# ascender_board.net
KiCad netlist of a schematic drawn in EAGLE
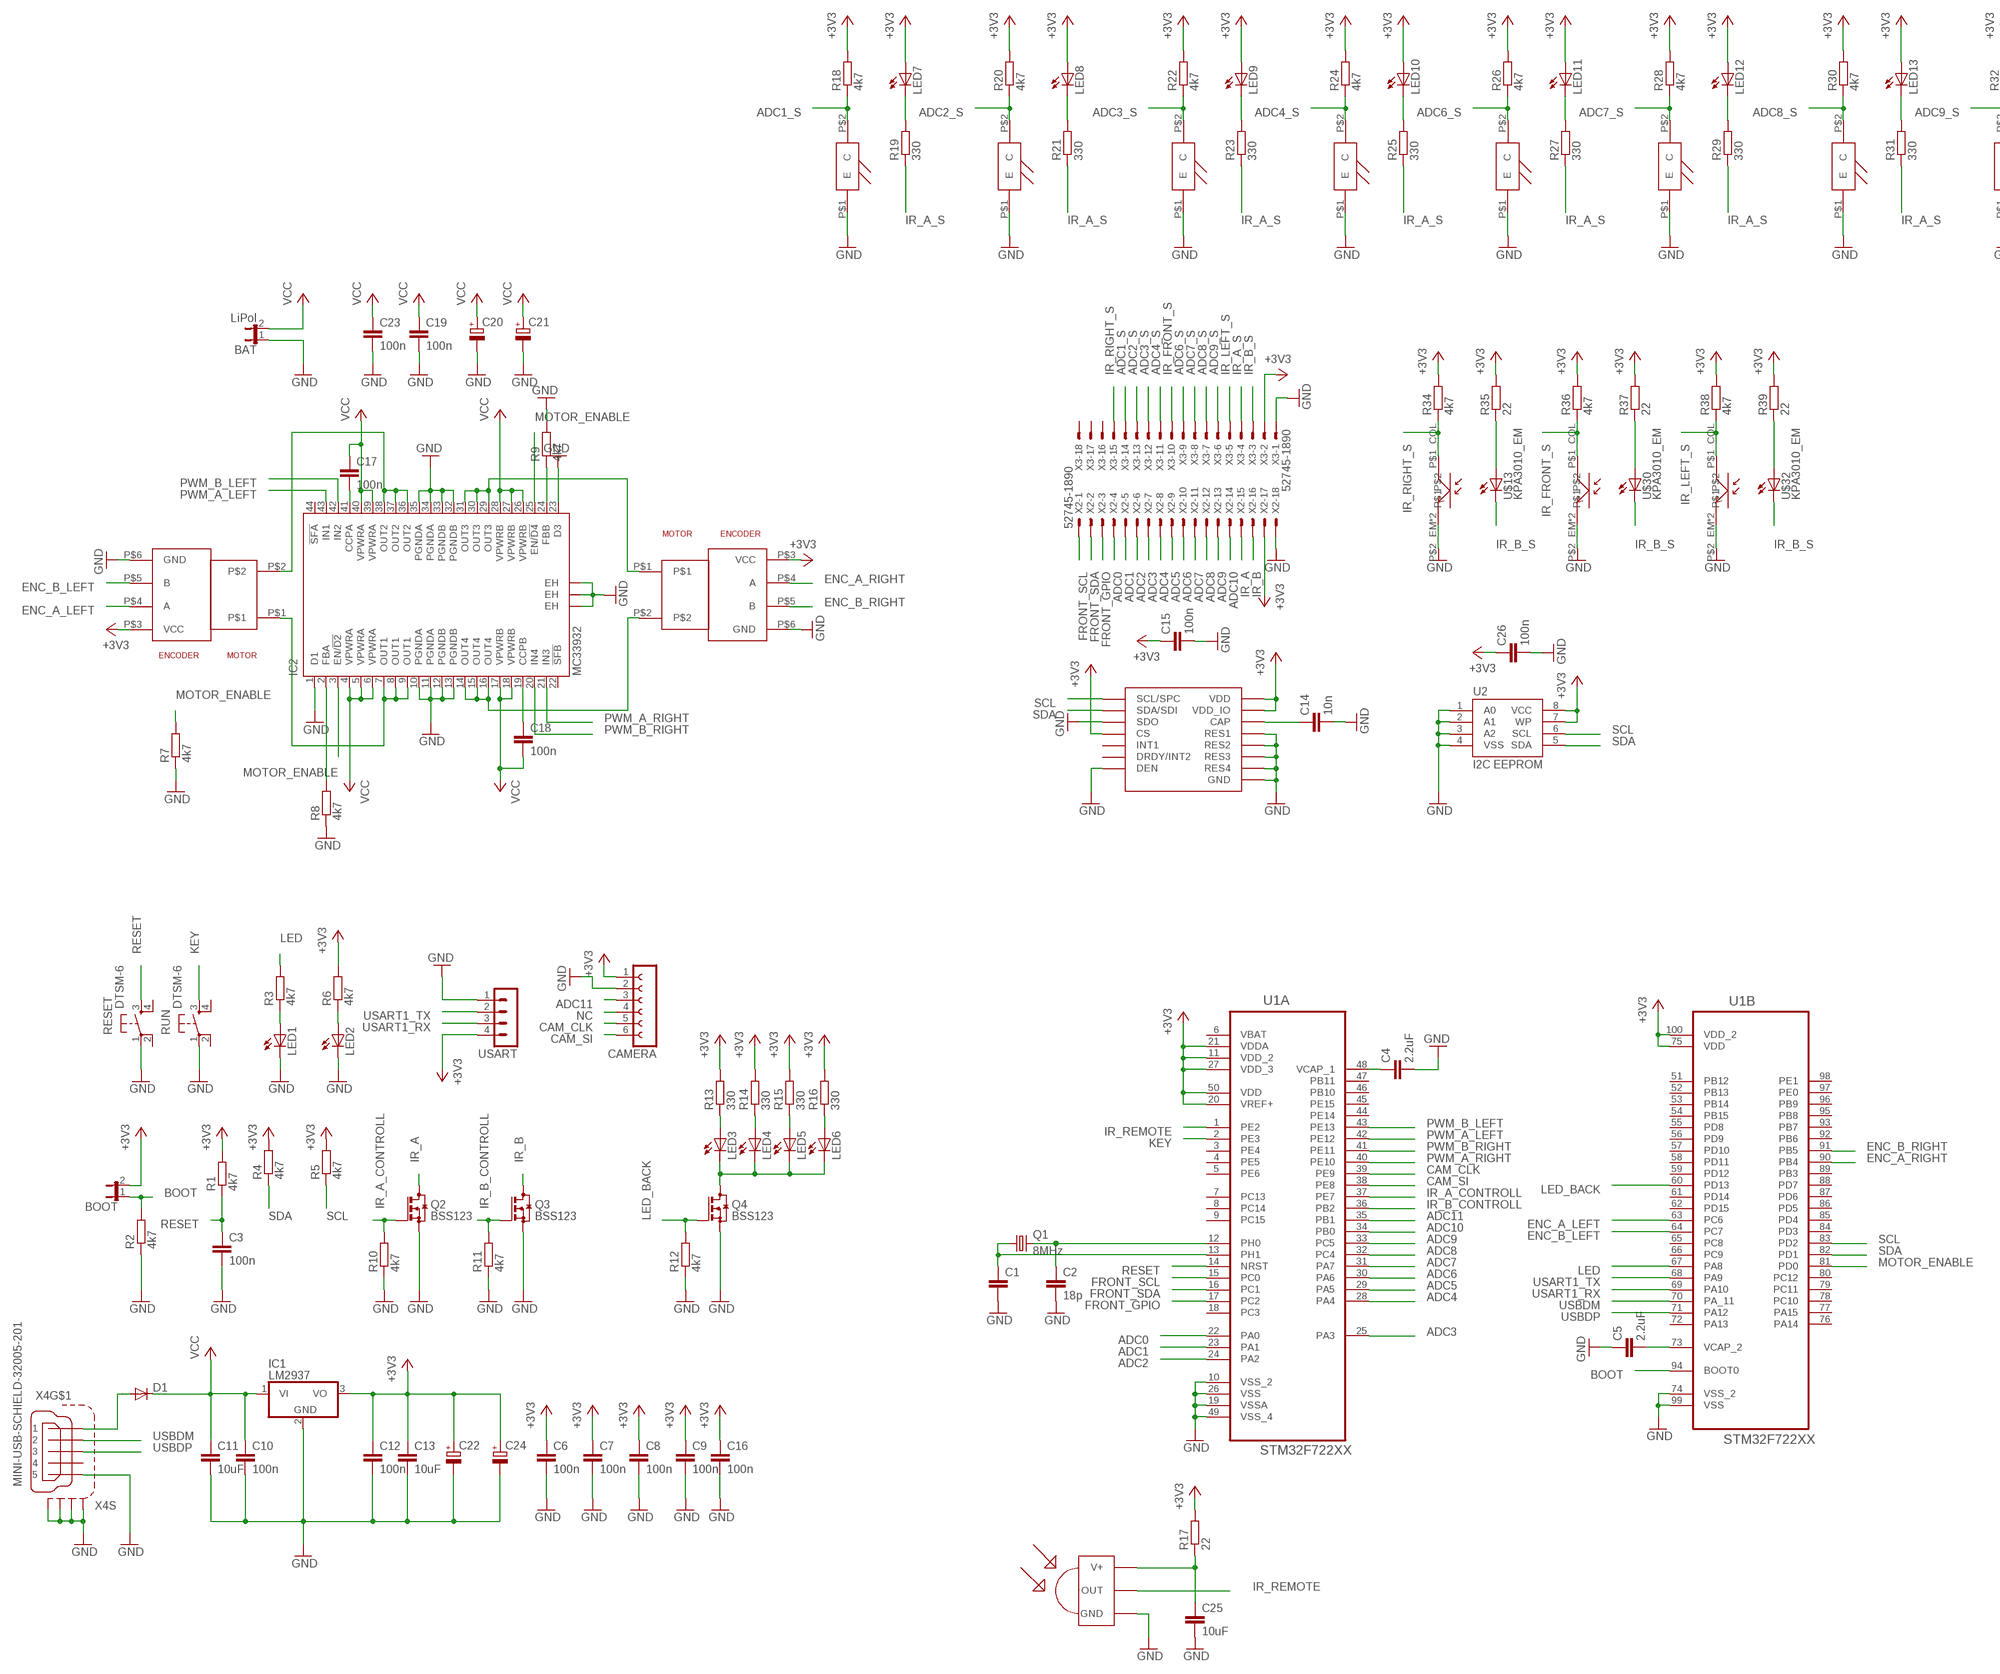
[diagram p0: schematic, sheet 1, part 1 of 2]
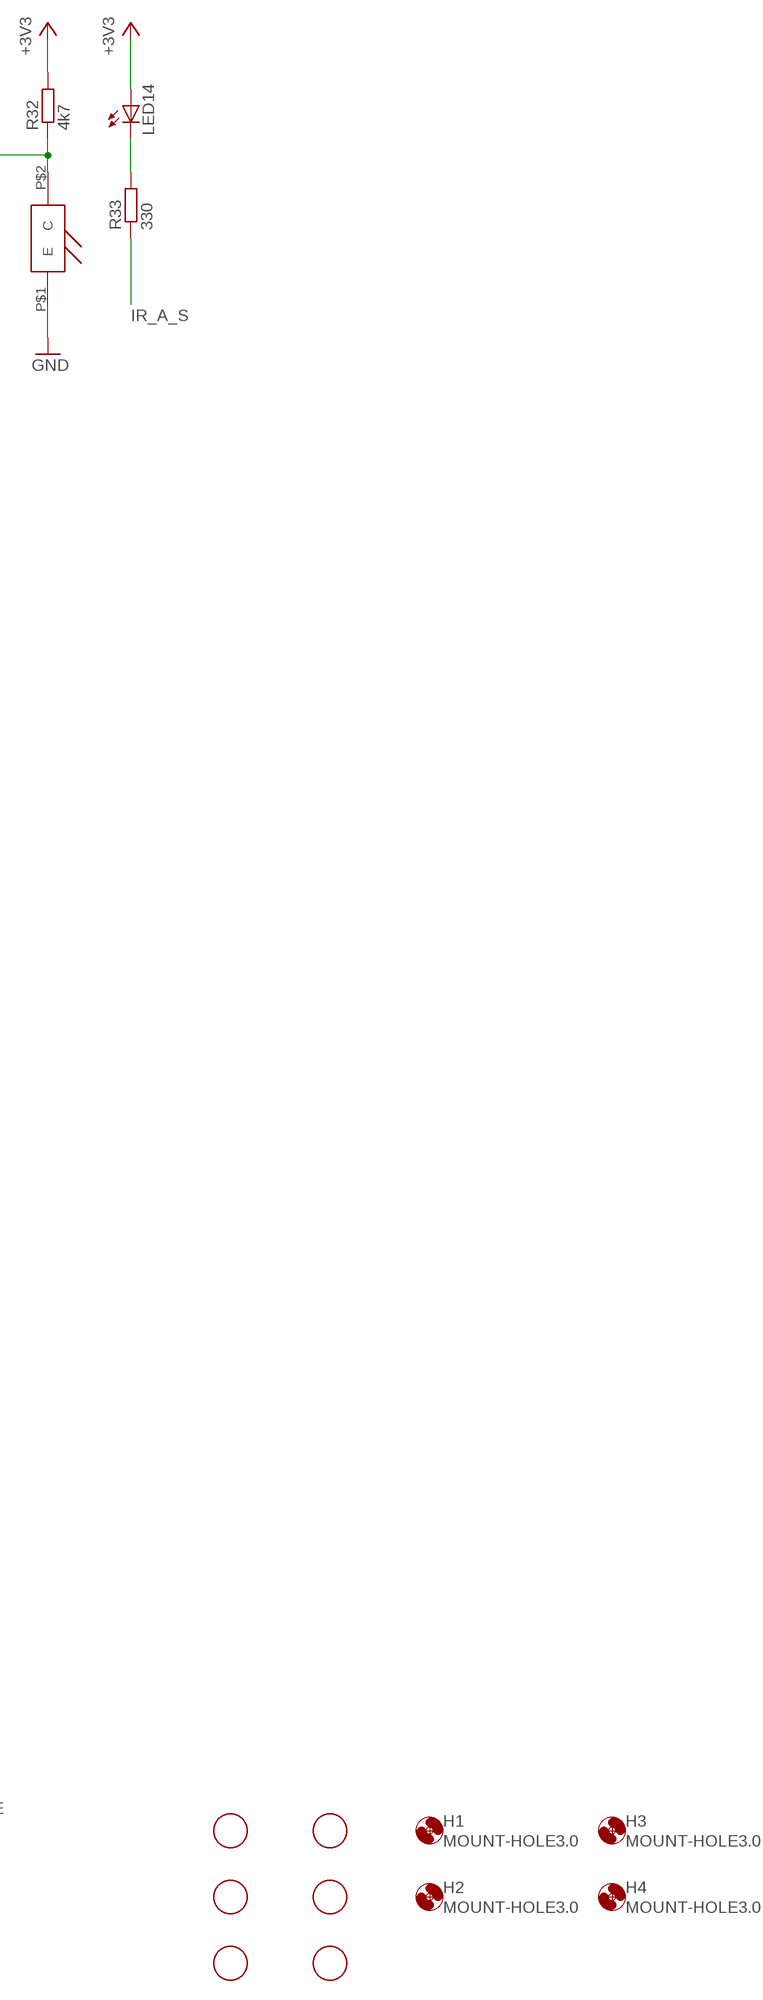
[diagram p1: schematic, sheet 1, part 2 of 2]

(export (version "E")
  (design (tool "Eeschema 10.0.6"))
  (components
    (comp (ref "BAT")
      (value "LiPol")
      (footprint "eagle-import:JP1")
      (libsource (lib "eagle-import") (part "JP1E"))
    )
    (comp (ref "BOOT")
      (value "JP1E")
      (footprint "eagle-import:JP1")
      (libsource (lib "eagle-import") (part "JP1E"))
    )
    (comp (ref "C1")
      (value "C-EUC0805")
      (footprint "eagle-import:C0805")
      (libsource (lib "eagle-import") (part "C-EUC0805"))
    )
    (comp (ref "C2")
      (value "18p")
      (footprint "eagle-import:C0805")
      (libsource (lib "eagle-import") (part "C-EUC0805"))
    )
    (comp (ref "C3")
      (value "100n")
      (footprint "eagle-import:C0805")
      (libsource (lib "eagle-import") (part "C-EUC0805"))
    )
    (comp (ref "C4")
      (value "2.2uF")
      (footprint "eagle-import:C0805")
      (libsource (lib "eagle-import") (part "C-EUC0805"))
    )
    (comp (ref "C5")
      (value "2.2uF")
      (footprint "eagle-import:C0805")
      (libsource (lib "eagle-import") (part "C-EUC0805"))
    )
    (comp (ref "C6")
      (value "100n")
      (footprint "eagle-import:C0805")
      (libsource (lib "eagle-import") (part "C-EUC0805"))
    )
    (comp (ref "C7")
      (value "100n")
      (footprint "eagle-import:C0805")
      (libsource (lib "eagle-import") (part "C-EUC0805"))
    )
    (comp (ref "C8")
      (value "100n")
      (footprint "eagle-import:C0805")
      (libsource (lib "eagle-import") (part "C-EUC0805"))
    )
    (comp (ref "C9")
      (value "100n")
      (footprint "eagle-import:C0805")
      (libsource (lib "eagle-import") (part "C-EUC0805"))
    )
    (comp (ref "C10")
      (value "100n")
      (footprint "eagle-import:C0805")
      (libsource (lib "eagle-import") (part "C-EUC0805"))
    )
    (comp (ref "C11")
      (value "10uF")
      (footprint "eagle-import:C0805")
      (libsource (lib "eagle-import") (part "C-EUC0805"))
    )
    (comp (ref "C12")
      (value "100n")
      (footprint "eagle-import:C0805")
      (libsource (lib "eagle-import") (part "C-EUC0805"))
    )
    (comp (ref "C13")
      (value "10uF")
      (footprint "eagle-import:C0805")
      (libsource (lib "eagle-import") (part "C-EUC0805"))
    )
    (comp (ref "C14")
      (value "10n")
      (footprint "eagle-import:C0805")
      (libsource (lib "eagle-import") (part "C-EUC0805"))
    )
    (comp (ref "C15")
      (value "100n")
      (footprint "eagle-import:C0805")
      (libsource (lib "eagle-import") (part "C-EUC0805"))
    )
    (comp (ref "C16")
      (value "100n")
      (footprint "eagle-import:C0805")
      (libsource (lib "eagle-import") (part "C-EUC0805"))
    )
    (comp (ref "C17")
      (value "100n")
      (footprint "eagle-import:C0805")
      (libsource (lib "eagle-import") (part "C-EUC0805"))
    )
    (comp (ref "C18")
      (value "100n")
      (footprint "eagle-import:C0805")
      (libsource (lib "eagle-import") (part "C-EUC0805"))
    )
    (comp (ref "C19")
      (value "100n")
      (footprint "eagle-import:C0805")
      (libsource (lib "eagle-import") (part "C-EUC0805"))
    )
    (comp (ref "C20")
      (value "CPOL-EU153CLV-0505")
      (footprint "eagle-import:153CLV-0505")
      (libsource (lib "eagle-import") (part "CPOL-EU153CLV-0505"))
    )
    (comp (ref "C21")
      (value "CPOL-EU153CLV-0505")
      (footprint "eagle-import:153CLV-0505")
      (libsource (lib "eagle-import") (part "CPOL-EU153CLV-0505"))
    )
    (comp (ref "C22")
      (value "CPOL-EU153CLV-0505")
      (footprint "eagle-import:153CLV-0505")
      (libsource (lib "eagle-import") (part "CPOL-EU153CLV-0505"))
    )
    (comp (ref "C23")
      (value "100n")
      (footprint "eagle-import:C0805")
      (libsource (lib "eagle-import") (part "C-EUC0805"))
    )
    (comp (ref "C24")
      (value "CPOL-EU153CLV-0505")
      (footprint "eagle-import:153CLV-0505")
      (libsource (lib "eagle-import") (part "CPOL-EU153CLV-0505"))
    )
    (comp (ref "C25")
      (value "10uF")
      (footprint "eagle-import:C0805")
      (libsource (lib "eagle-import") (part "C-EUC0805"))
    )
    (comp (ref "C26")
      (value "100n")
      (footprint "eagle-import:C0805")
      (libsource (lib "eagle-import") (part "C-EUC0805"))
    )
    (comp (ref "CAMERA")
      (value "FE06-1")
      (footprint "eagle-import:FE06")
      (libsource (lib "eagle-import") (part "FE06-1"))
    )
    (comp (ref "D1")
      (value "DIODE-DO-214AC")
      (footprint "eagle-import:DO-214AC")
      (libsource (lib "eagle-import") (part "DIODE-DO-214AC"))
    )
    (comp (ref "H1")
      (value "MOUNT-HOLE3.0")
      (footprint "eagle-import:3,0")
      (libsource (lib "eagle-import") (part "MOUNT-HOLE3.0"))
    )
    (comp (ref "H2")
      (value "MOUNT-HOLE3.0")
      (footprint "eagle-import:3,0")
      (libsource (lib "eagle-import") (part "MOUNT-HOLE3.0"))
    )
    (comp (ref "H3")
      (value "MOUNT-HOLE3.0")
      (footprint "eagle-import:3,0")
      (libsource (lib "eagle-import") (part "MOUNT-HOLE3.0"))
    )
    (comp (ref "H4")
      (value "MOUNT-HOLE3.0")
      (footprint "eagle-import:3,0")
      (libsource (lib "eagle-import") (part "MOUNT-HOLE3.0"))
    )
    (comp (ref "IC1")
      (value "LM2937")
      (footprint "eagle-import:TO263-3")
      (libsource (lib "eagle-import") (part "LM2937"))
    )
    (comp (ref "IC2")
      (value "MC33932")
      (footprint "eagle-import:HSOP44")
      (fields (field (name "MPN") "MC33932VW"))
      (libsource (lib "eagle-import") (part "MC33932"))
    )
    (comp (ref "LED1")
      (value "LEDCHIPLED_1206")
      (footprint "eagle-import:CHIPLED_1206")
      (libsource (lib "eagle-import") (part "LEDCHIPLED_1206"))
    )
    (comp (ref "LED2")
      (value "LEDCHIPLED_1206")
      (footprint "eagle-import:CHIPLED_1206")
      (libsource (lib "eagle-import") (part "LEDCHIPLED_1206"))
    )
    (comp (ref "LED3")
      (value "LEDCHIPLED_1206")
      (footprint "eagle-import:CHIPLED_1206")
      (libsource (lib "eagle-import") (part "LEDCHIPLED_1206"))
    )
    (comp (ref "LED4")
      (value "LEDCHIPLED_1206")
      (footprint "eagle-import:CHIPLED_1206")
      (libsource (lib "eagle-import") (part "LEDCHIPLED_1206"))
    )
    (comp (ref "LED5")
      (value "LEDCHIPLED_1206")
      (footprint "eagle-import:CHIPLED_1206")
      (libsource (lib "eagle-import") (part "LEDCHIPLED_1206"))
    )
    (comp (ref "LED6")
      (value "LEDCHIPLED_1206")
      (footprint "eagle-import:CHIPLED_1206")
      (libsource (lib "eagle-import") (part "LEDCHIPLED_1206"))
    )
    (comp (ref "LED7")
      (value "LEDCHIPLED_1206")
      (footprint "eagle-import:CHIPLED_1206")
      (libsource (lib "eagle-import") (part "LEDCHIPLED_1206"))
    )
    (comp (ref "LED8")
      (value "LEDCHIPLED_1206")
      (footprint "eagle-import:CHIPLED_1206")
      (libsource (lib "eagle-import") (part "LEDCHIPLED_1206"))
    )
    (comp (ref "LED9")
      (value "LEDCHIPLED_1206")
      (footprint "eagle-import:CHIPLED_1206")
      (libsource (lib "eagle-import") (part "LEDCHIPLED_1206"))
    )
    (comp (ref "LED10")
      (value "LEDCHIPLED_1206")
      (footprint "eagle-import:CHIPLED_1206")
      (libsource (lib "eagle-import") (part "LEDCHIPLED_1206"))
    )
    (comp (ref "LED11")
      (value "LEDCHIPLED_1206")
      (footprint "eagle-import:CHIPLED_1206")
      (libsource (lib "eagle-import") (part "LEDCHIPLED_1206"))
    )
    (comp (ref "LED12")
      (value "LEDCHIPLED_1206")
      (footprint "eagle-import:CHIPLED_1206")
      (libsource (lib "eagle-import") (part "LEDCHIPLED_1206"))
    )
    (comp (ref "LED13")
      (value "LEDCHIPLED_1206")
      (footprint "eagle-import:CHIPLED_1206")
      (libsource (lib "eagle-import") (part "LEDCHIPLED_1206"))
    )
    (comp (ref "LED14")
      (value "LEDCHIPLED_1206")
      (footprint "eagle-import:CHIPLED_1206")
      (libsource (lib "eagle-import") (part "LEDCHIPLED_1206"))
    )
    (comp (ref "Q1")
      (value "8MHz")
      (footprint "eagle-import:CTS406")
      (libsource (lib "eagle-import") (part "CRYSTALCTS406"))
    )
    (comp (ref "Q2")
      (value "BSS123")
      (footprint "eagle-import:SOT23")
      (libsource (lib "eagle-import") (part "BSS123"))
    )
    (comp (ref "Q3")
      (value "BSS123")
      (footprint "eagle-import:SOT23")
      (libsource (lib "eagle-import") (part "BSS123"))
    )
    (comp (ref "Q4")
      (value "BSS123")
      (footprint "eagle-import:SOT23")
      (libsource (lib "eagle-import") (part "BSS123"))
    )
    (comp (ref "R1")
      (value "4k7")
      (footprint "eagle-import:M0805")
      (libsource (lib "eagle-import") (part "R-EU_M0805"))
    )
    (comp (ref "R2")
      (value "4k7")
      (footprint "eagle-import:M0805")
      (libsource (lib "eagle-import") (part "R-EU_M0805"))
    )
    (comp (ref "R3")
      (value "4k7")
      (footprint "eagle-import:M0805")
      (libsource (lib "eagle-import") (part "R-EU_M0805"))
    )
    (comp (ref "R4")
      (value "4k7")
      (footprint "eagle-import:M0805")
      (libsource (lib "eagle-import") (part "R-EU_M0805"))
    )
    (comp (ref "R5")
      (value "4k7")
      (footprint "eagle-import:M0805")
      (libsource (lib "eagle-import") (part "R-EU_M0805"))
    )
    (comp (ref "R6")
      (value "4k7")
      (footprint "eagle-import:M0805")
      (libsource (lib "eagle-import") (part "R-EU_M0805"))
    )
    (comp (ref "R7")
      (value "4k7")
      (footprint "eagle-import:M0805")
      (libsource (lib "eagle-import") (part "R-EU_M0805"))
    )
    (comp (ref "R8")
      (value "4k7")
      (footprint "eagle-import:M0805")
      (libsource (lib "eagle-import") (part "R-EU_M0805"))
    )
    (comp (ref "R9")
      (value "4k7")
      (footprint "eagle-import:M0805")
      (libsource (lib "eagle-import") (part "R-EU_M0805"))
    )
    (comp (ref "R10")
      (value "4k7")
      (footprint "eagle-import:M0805")
      (libsource (lib "eagle-import") (part "R-EU_M0805"))
    )
    (comp (ref "R11")
      (value "4k7")
      (footprint "eagle-import:M0805")
      (libsource (lib "eagle-import") (part "R-EU_M0805"))
    )
    (comp (ref "R12")
      (value "4k7")
      (footprint "eagle-import:M0805")
      (libsource (lib "eagle-import") (part "R-EU_M0805"))
    )
    (comp (ref "R13")
      (value "330")
      (footprint "eagle-import:M0805")
      (libsource (lib "eagle-import") (part "R-EU_M0805"))
    )
    (comp (ref "R14")
      (value "330")
      (footprint "eagle-import:M0805")
      (libsource (lib "eagle-import") (part "R-EU_M0805"))
    )
    (comp (ref "R15")
      (value "330")
      (footprint "eagle-import:M0805")
      (libsource (lib "eagle-import") (part "R-EU_M0805"))
    )
    (comp (ref "R16")
      (value "330")
      (footprint "eagle-import:M0805")
      (libsource (lib "eagle-import") (part "R-EU_M0805"))
    )
    (comp (ref "R17")
      (value "22")
      (footprint "eagle-import:M0805")
      (libsource (lib "eagle-import") (part "R-EU_M0805"))
    )
    (comp (ref "R18")
      (value "4k7")
      (footprint "eagle-import:M0805")
      (libsource (lib "eagle-import") (part "R-EU_M0805"))
    )
    (comp (ref "R19")
      (value "330")
      (footprint "eagle-import:M0805")
      (libsource (lib "eagle-import") (part "R-EU_M0805"))
    )
    (comp (ref "R20")
      (value "4k7")
      (footprint "eagle-import:M0805")
      (libsource (lib "eagle-import") (part "R-EU_M0805"))
    )
    (comp (ref "R21")
      (value "330")
      (footprint "eagle-import:M0805")
      (libsource (lib "eagle-import") (part "R-EU_M0805"))
    )
    (comp (ref "R22")
      (value "4k7")
      (footprint "eagle-import:M0805")
      (libsource (lib "eagle-import") (part "R-EU_M0805"))
    )
    (comp (ref "R23")
      (value "330")
      (footprint "eagle-import:M0805")
      (libsource (lib "eagle-import") (part "R-EU_M0805"))
    )
    (comp (ref "R24")
      (value "4k7")
      (footprint "eagle-import:M0805")
      (libsource (lib "eagle-import") (part "R-EU_M0805"))
    )
    (comp (ref "R25")
      (value "330")
      (footprint "eagle-import:M0805")
      (libsource (lib "eagle-import") (part "R-EU_M0805"))
    )
    (comp (ref "R26")
      (value "4k7")
      (footprint "eagle-import:M0805")
      (libsource (lib "eagle-import") (part "R-EU_M0805"))
    )
    (comp (ref "R27")
      (value "330")
      (footprint "eagle-import:M0805")
      (libsource (lib "eagle-import") (part "R-EU_M0805"))
    )
    (comp (ref "R28")
      (value "4k7")
      (footprint "eagle-import:M0805")
      (libsource (lib "eagle-import") (part "R-EU_M0805"))
    )
    (comp (ref "R29")
      (value "330")
      (footprint "eagle-import:M0805")
      (libsource (lib "eagle-import") (part "R-EU_M0805"))
    )
    (comp (ref "R30")
      (value "4k7")
      (footprint "eagle-import:M0805")
      (libsource (lib "eagle-import") (part "R-EU_M0805"))
    )
    (comp (ref "R31")
      (value "330")
      (footprint "eagle-import:M0805")
      (libsource (lib "eagle-import") (part "R-EU_M0805"))
    )
    (comp (ref "R32")
      (value "4k7")
      (footprint "eagle-import:M0805")
      (libsource (lib "eagle-import") (part "R-EU_M0805"))
    )
    (comp (ref "R33")
      (value "330")
      (footprint "eagle-import:M0805")
      (libsource (lib "eagle-import") (part "R-EU_M0805"))
    )
    (comp (ref "R34")
      (value "4k7")
      (footprint "eagle-import:M0805")
      (libsource (lib "eagle-import") (part "R-EU_M0805"))
    )
    (comp (ref "R35")
      (value "22")
      (footprint "eagle-import:M0805")
      (libsource (lib "eagle-import") (part "R-EU_M0805"))
    )
    (comp (ref "R36")
      (value "4k7")
      (footprint "eagle-import:M0805")
      (libsource (lib "eagle-import") (part "R-EU_M0805"))
    )
    (comp (ref "R37")
      (value "22")
      (footprint "eagle-import:M0805")
      (libsource (lib "eagle-import") (part "R-EU_M0805"))
    )
    (comp (ref "R38")
      (value "4k7")
      (footprint "eagle-import:M0805")
      (libsource (lib "eagle-import") (part "R-EU_M0805"))
    )
    (comp (ref "R39")
      (value "22")
      (footprint "eagle-import:M0805")
      (libsource (lib "eagle-import") (part "R-EU_M0805"))
    )
    (comp (ref "RESET")
      (value "DTSM-6")
      (footprint "eagle-import:DTSM-6")
      (libsource (lib "eagle-import") (part "DTSM-6"))
    )
    (comp (ref "RUN")
      (value "DTSM-6")
      (footprint "eagle-import:DTSM-6")
      (libsource (lib "eagle-import") (part "DTSM-6"))
    )
    (comp (ref "U$1")
      (value "POLOLU_GEAR_MOTORPOLO")
      (footprint "eagle-import:POLOLU_GEAR_MOTOR")
      (libsource (lib "eagle-import") (part "POLOLU_GEAR_MOTORPOLO"))
    )
    (comp (ref "U$2")
      (value "ST_L3GD20H")
      (footprint "eagle-import:ST_LGA16L")
      (libsource (lib "eagle-import") (part "ST_L3GD20H"))
    )
    (comp (ref "U$3")
      (value "FIDUCIAL")
      (footprint "eagle-import:FIDUCIAL_1MM")
      (libsource (lib "eagle-import") (part "FIDUCIAL"))
    )
    (comp (ref "U$4")
      (value "FIDUCIAL")
      (footprint "eagle-import:FIDUCIAL_1MM")
      (libsource (lib "eagle-import") (part "FIDUCIAL"))
    )
    (comp (ref "U$5")
      (value "FIDUCIAL")
      (footprint "eagle-import:FIDUCIAL_1MM")
      (libsource (lib "eagle-import") (part "FIDUCIAL"))
    )
    (comp (ref "U$6")
      (value "FIDUCIAL")
      (footprint "eagle-import:FIDUCIAL_1MM")
      (libsource (lib "eagle-import") (part "FIDUCIAL"))
    )
    (comp (ref "U$7")
      (value "FIDUCIAL")
      (footprint "eagle-import:FIDUCIAL_1MM")
      (libsource (lib "eagle-import") (part "FIDUCIAL"))
    )
    (comp (ref "U$8")
      (value "FIDUCIAL")
      (footprint "eagle-import:FIDUCIAL_1MM")
      (libsource (lib "eagle-import") (part "FIDUCIAL"))
    )
    (comp (ref "U$9")
      (value "TSOP4830")
      (footprint "eagle-import:TSOP18XX")
      (libsource (lib "eagle-import") (part "TSOP4830"))
    )
    (comp (ref "U$10")
      (value "POLOLU_GEAR_MOTORPOLO")
      (footprint "eagle-import:POLOLU_GEAR_MOTOR")
      (libsource (lib "eagle-import") (part "POLOLU_GEAR_MOTORPOLO"))
    )
    (comp (ref "U$11")
      (value "SFH3710")
      (footprint "eagle-import:SFH3710")
      (libsource (lib "eagle-import") (part "SFH3710"))
    )
    (comp (ref "U$12")
      (value "KPA3010")
      (footprint "eagle-import:KPA3010")
      (libsource (lib "eagle-import") (part "KPA3010"))
    )
    (comp (ref "U$13")
      (value "KPA3010_EM")
      (footprint "eagle-import:KPA3010")
      (libsource (lib "eagle-import") (part "KPA3010_EM"))
    )
    (comp (ref "U$14")
      (value "SFH3710")
      (footprint "eagle-import:SFH3710")
      (libsource (lib "eagle-import") (part "SFH3710"))
    )
    (comp (ref "U$15")
      (value "SFH3710")
      (footprint "eagle-import:SFH3710")
      (libsource (lib "eagle-import") (part "SFH3710"))
    )
    (comp (ref "U$16")
      (value "SFH3710")
      (footprint "eagle-import:SFH3710")
      (libsource (lib "eagle-import") (part "SFH3710"))
    )
    (comp (ref "U$17")
      (value "SFH3710")
      (footprint "eagle-import:SFH3710")
      (libsource (lib "eagle-import") (part "SFH3710"))
    )
    (comp (ref "U$18")
      (value "SFH3710")
      (footprint "eagle-import:SFH3710")
      (libsource (lib "eagle-import") (part "SFH3710"))
    )
    (comp (ref "U$19")
      (value "SFH3710")
      (footprint "eagle-import:SFH3710")
      (libsource (lib "eagle-import") (part "SFH3710"))
    )
    (comp (ref "U$20")
      (value "SFH3710")
      (footprint "eagle-import:SFH3710")
      (libsource (lib "eagle-import") (part "SFH3710"))
    )
    (comp (ref "U$29")
      (value "KPA3010")
      (footprint "eagle-import:KPA3010")
      (libsource (lib "eagle-import") (part "KPA3010"))
    )
    (comp (ref "U$30")
      (value "KPA3010_EM")
      (footprint "eagle-import:KPA3010")
      (libsource (lib "eagle-import") (part "KPA3010_EM"))
    )
    (comp (ref "U$31")
      (value "KPA3010")
      (footprint "eagle-import:KPA3010")
      (libsource (lib "eagle-import") (part "KPA3010"))
    )
    (comp (ref "U$32")
      (value "KPA3010_EM")
      (footprint "eagle-import:KPA3010")
      (libsource (lib "eagle-import") (part "KPA3010_EM"))
    )
    (comp (ref "U1")
      (value "STM32F722XX")
      (footprint "eagle-import:QFP50P1600X1600X160-100N")
      (fields (field (name "MPN") "STM32F407VET6"))
      (libsource (lib "eagle-import") (part "STM32F722XX"))
    )
    (comp (ref "U2")
      (value "I2C EEPROM")
      (footprint "eagle-import:SO08-EIAJ")
      (libsource (lib "eagle-import") (part "EEPROM-I2CEIAJ"))
    )
    (comp (ref "USART")
      (value "MA04-1")
      (footprint "eagle-import:MA04-1")
      (libsource (lib "eagle-import") (part "MA04-1"))
    )
    (comp (ref "X2")
      (value "52745-1890")
      (footprint "eagle-import:52745-1890")
      (libsource (lib "eagle-import") (part "52745-1890"))
    )
    (comp (ref "X3")
      (value "52745-1890")
      (footprint "eagle-import:52745-1890")
      (libsource (lib "eagle-import") (part "52745-1890"))
    )
    (comp (ref "X4")
      (value "MINI-USB-SCHIELD-32005-201")
      (footprint "eagle-import:32005-201")
      (libsource (lib "eagle-import") (part "MINI-USB-SCHIELD-32005-201"))
    )
  )
  (nets
    (net (code "1") (name "+3V3") (class "Default")
      (node (ref "BOOT") (pin "2") (pinfunction "2_2") (pintype "passive"))
      (node (ref "C12") (pin "1") (pinfunction "1_1") (pintype "passive"))
      (node (ref "C13") (pin "1") (pinfunction "1_1") (pintype "passive"))
      (node (ref "C15") (pin "1") (pinfunction "1_1") (pintype "passive"))
      (node (ref "C16") (pin "1") (pinfunction "1_1") (pintype "passive"))
      (node (ref "C22") (pin "+") (pinfunction "+_+") (pintype "passive"))
      (node (ref "C24") (pin "+") (pinfunction "+_+") (pintype "passive"))
      (node (ref "C26") (pin "1") (pinfunction "1_1") (pintype "passive"))
      (node (ref "C6") (pin "1") (pinfunction "1_1") (pintype "passive"))
      (node (ref "C7") (pin "1") (pinfunction "1_1") (pintype "passive"))
      (node (ref "C8") (pin "1") (pinfunction "1_1") (pintype "passive"))
      (node (ref "C9") (pin "1") (pinfunction "1_1") (pintype "passive"))
      (node (ref "CAMERA") (pin "1") (pinfunction "1_1") (pintype "passive"))
      (node (ref "IC1") (pin "3") (pinfunction "VO_3") (pintype "passive"))
      (node (ref "LED10") (pin "A") (pinfunction "A_A") (pintype "passive"))
      (node (ref "LED11") (pin "A") (pinfunction "A_A") (pintype "passive"))
      (node (ref "LED12") (pin "A") (pinfunction "A_A") (pintype "passive"))
      (node (ref "LED13") (pin "A") (pinfunction "A_A") (pintype "passive"))
      (node (ref "LED14") (pin "A") (pinfunction "A_A") (pintype "passive"))
      (node (ref "LED7") (pin "A") (pinfunction "A_A") (pintype "passive"))
      (node (ref "LED8") (pin "A") (pinfunction "A_A") (pintype "passive"))
      (node (ref "LED9") (pin "A") (pinfunction "A_A") (pintype "passive"))
      (node (ref "R1") (pin "2") (pinfunction "2_2") (pintype "passive"))
      (node (ref "R13") (pin "2") (pinfunction "2_2") (pintype "passive"))
      (node (ref "R14") (pin "2") (pinfunction "2_2") (pintype "passive"))
      (node (ref "R15") (pin "2") (pinfunction "2_2") (pintype "passive"))
      (node (ref "R16") (pin "2") (pinfunction "2_2") (pintype "passive"))
      (node (ref "R17") (pin "2") (pinfunction "2_2") (pintype "passive"))
      (node (ref "R18") (pin "2") (pinfunction "2_2") (pintype "passive"))
      (node (ref "R20") (pin "2") (pinfunction "2_2") (pintype "passive"))
      (node (ref "R22") (pin "2") (pinfunction "2_2") (pintype "passive"))
      (node (ref "R24") (pin "2") (pinfunction "2_2") (pintype "passive"))
      (node (ref "R26") (pin "2") (pinfunction "2_2") (pintype "passive"))
      (node (ref "R28") (pin "2") (pinfunction "2_2") (pintype "passive"))
      (node (ref "R30") (pin "2") (pinfunction "2_2") (pintype "passive"))
      (node (ref "R32") (pin "2") (pinfunction "2_2") (pintype "passive"))
      (node (ref "R34") (pin "2") (pinfunction "2_2") (pintype "passive"))
      (node (ref "R35") (pin "2") (pinfunction "2_2") (pintype "passive"))
      (node (ref "R36") (pin "2") (pinfunction "2_2") (pintype "passive"))
      (node (ref "R37") (pin "2") (pinfunction "2_2") (pintype "passive"))
      (node (ref "R38") (pin "2") (pinfunction "2_2") (pintype "passive"))
      (node (ref "R39") (pin "2") (pinfunction "2_2") (pintype "passive"))
      (node (ref "R4") (pin "2") (pinfunction "2_2") (pintype "passive"))
      (node (ref "R5") (pin "2") (pinfunction "2_2") (pintype "passive"))
      (node (ref "R6") (pin "2") (pinfunction "2_2") (pintype "passive"))
      (node (ref "U$1") (pin "P$3") (pinfunction "VCC_P$3") (pintype "bidirectional"))
      (node (ref "U$10") (pin "P$3") (pinfunction "VCC_P$3") (pintype "bidirectional"))
      (node (ref "U$2") (pin "P$1") (pinfunction "VDD_IO_P$1") (pintype "power_in"))
      (node (ref "U$2") (pin "P$16") (pinfunction "VDD_P$16") (pintype "power_in"))
      (node (ref "U$2") (pin "P$5") (pinfunction "CS_P$5") (pintype "bidirectional"))
      (node (ref "U1") (pin "100") (pinfunction "VDD_2_100") (pintype "power_in"))
      (node (ref "U1") (pin "11") (pinfunction "VDD_2_11") (pintype "power_in"))
      (node (ref "U1") (pin "20") (pinfunction "VREF+_20") (pintype "power_in"))
      (node (ref "U1") (pin "21") (pinfunction "VDDA_21") (pintype "power_in"))
      (node (ref "U1") (pin "27") (pinfunction "VDD_3_27") (pintype "power_in"))
      (node (ref "U1") (pin "50") (pinfunction "VDD_50") (pintype "power_in"))
      (node (ref "U1") (pin "75") (pinfunction "VDD_75") (pintype "power_in"))
      (node (ref "U2") (pin "7") (pinfunction "WP_7") (pintype "bidirectional"))
      (node (ref "U2") (pin "8") (pinfunction "VCC_8") (pintype "power_in"))
      (node (ref "USART") (pin "4") (pinfunction "4_4") (pintype "passive"))
      (node (ref "X2") (pin "17") (pinfunction "S_17") (pintype "passive"))
      (node (ref "X3") (pin "2") (pinfunction "S_2") (pintype "passive"))
    )
    (net (code "2") (name "/ADC0") (class "Default")
      (node (ref "U1") (pin "22") (pinfunction "PA0_22") (pintype "bidirectional"))
      (node (ref "X2") (pin "4") (pinfunction "S_4") (pintype "passive"))
    )
    (net (code "3") (name "/ADC1") (class "Default")
      (node (ref "U1") (pin "23") (pinfunction "PA1_23") (pintype "bidirectional"))
      (node (ref "X2") (pin "5") (pinfunction "S_5") (pintype "passive"))
    )
    (net (code "4") (name "/ADC1_S") (class "Default")
      (node (ref "R18") (pin "1") (pinfunction "1_1") (pintype "passive"))
      (node (ref "U$11") (pin "P$2") (pinfunction "C_P$2") (pintype "bidirectional"))
      (node (ref "X3") (pin "14") (pinfunction "S_14") (pintype "passive"))
    )
    (net (code "5") (name "/ADC2") (class "Default")
      (node (ref "U1") (pin "24") (pinfunction "PA2_24") (pintype "bidirectional"))
      (node (ref "X2") (pin "6") (pinfunction "S_6") (pintype "passive"))
    )
    (net (code "6") (name "/ADC2_S") (class "Default")
      (node (ref "R20") (pin "1") (pinfunction "1_1") (pintype "passive"))
      (node (ref "U$14") (pin "P$2") (pinfunction "C_P$2") (pintype "bidirectional"))
      (node (ref "X3") (pin "13") (pinfunction "S_13") (pintype "passive"))
    )
    (net (code "7") (name "/ADC3") (class "Default")
      (node (ref "U1") (pin "25") (pinfunction "PA3_25") (pintype "bidirectional"))
      (node (ref "X2") (pin "7") (pinfunction "S_7") (pintype "passive"))
    )
    (net (code "8") (name "/ADC3_S") (class "Default")
      (node (ref "R22") (pin "1") (pinfunction "1_1") (pintype "passive"))
      (node (ref "U$15") (pin "P$2") (pinfunction "C_P$2") (pintype "bidirectional"))
      (node (ref "X3") (pin "12") (pinfunction "S_12") (pintype "passive"))
    )
    (net (code "9") (name "/ADC4") (class "Default")
      (node (ref "U1") (pin "28") (pinfunction "PA4_28") (pintype "bidirectional"))
      (node (ref "X2") (pin "8") (pinfunction "S_8") (pintype "passive"))
    )
    (net (code "10") (name "/ADC4_S") (class "Default")
      (node (ref "R24") (pin "1") (pinfunction "1_1") (pintype "passive"))
      (node (ref "U$16") (pin "P$2") (pinfunction "C_P$2") (pintype "bidirectional"))
      (node (ref "X3") (pin "11") (pinfunction "S_11") (pintype "passive"))
    )
    (net (code "11") (name "/ADC5") (class "Default")
      (node (ref "U1") (pin "29") (pinfunction "PA5_29") (pintype "bidirectional"))
      (node (ref "X2") (pin "9") (pinfunction "S_9") (pintype "passive"))
    )
    (net (code "12") (name "/ADC6") (class "Default")
      (node (ref "U1") (pin "30") (pinfunction "PA6_30") (pintype "bidirectional"))
      (node (ref "X2") (pin "10") (pinfunction "S_10") (pintype "passive"))
    )
    (net (code "13") (name "/ADC6_S") (class "Default")
      (node (ref "R26") (pin "1") (pinfunction "1_1") (pintype "passive"))
      (node (ref "U$17") (pin "P$2") (pinfunction "C_P$2") (pintype "bidirectional"))
      (node (ref "X3") (pin "9") (pinfunction "S_9") (pintype "passive"))
    )
    (net (code "14") (name "/ADC7") (class "Default")
      (node (ref "U1") (pin "31") (pinfunction "PA7_31") (pintype "bidirectional"))
      (node (ref "X2") (pin "11") (pinfunction "S_11") (pintype "passive"))
    )
    (net (code "15") (name "/ADC7_S") (class "Default")
      (node (ref "R28") (pin "1") (pinfunction "1_1") (pintype "passive"))
      (node (ref "U$18") (pin "P$2") (pinfunction "C_P$2") (pintype "bidirectional"))
      (node (ref "X3") (pin "8") (pinfunction "S_8") (pintype "passive"))
    )
    (net (code "16") (name "/ADC8") (class "Default")
      (node (ref "U1") (pin "32") (pinfunction "PC4_32") (pintype "bidirectional"))
      (node (ref "X2") (pin "12") (pinfunction "S_12") (pintype "passive"))
    )
    (net (code "17") (name "/ADC8_S") (class "Default")
      (node (ref "R30") (pin "1") (pinfunction "1_1") (pintype "passive"))
      (node (ref "U$19") (pin "P$2") (pinfunction "C_P$2") (pintype "bidirectional"))
      (node (ref "X3") (pin "7") (pinfunction "S_7") (pintype "passive"))
    )
    (net (code "18") (name "/ADC9") (class "Default")
      (node (ref "U1") (pin "33") (pinfunction "PC5_33") (pintype "bidirectional"))
      (node (ref "X2") (pin "13") (pinfunction "S_13") (pintype "passive"))
    )
    (net (code "19") (name "/ADC9_S") (class "Default")
      (node (ref "R32") (pin "1") (pinfunction "1_1") (pintype "passive"))
      (node (ref "U$20") (pin "P$2") (pinfunction "C_P$2") (pintype "bidirectional"))
      (node (ref "X3") (pin "6") (pinfunction "S_6") (pintype "passive"))
    )
    (net (code "20") (name "/ADC10") (class "Default")
      (node (ref "U1") (pin "34") (pinfunction "PB0_34") (pintype "bidirectional"))
      (node (ref "X2") (pin "14") (pinfunction "S_14") (pintype "passive"))
    )
    (net (code "21") (name "/ADC11") (class "Default")
      (node (ref "CAMERA") (pin "3") (pinfunction "3_3") (pintype "passive"))
      (node (ref "U1") (pin "35") (pinfunction "PB1_35") (pintype "bidirectional"))
    )
    (net (code "22") (name "/BOOT") (class "Default")
      (node (ref "BOOT") (pin "1") (pinfunction "1_1") (pintype "passive"))
      (node (ref "R2") (pin "2") (pinfunction "2_2") (pintype "passive"))
      (node (ref "U1") (pin "94") (pinfunction "BOOT0_94") (pintype "input"))
    )
    (net (code "23") (name "/CAM_CLK") (class "Default")
      (node (ref "CAMERA") (pin "5") (pinfunction "5_5") (pintype "passive"))
      (node (ref "U1") (pin "39") (pinfunction "PE9_39") (pintype "bidirectional"))
    )
    (net (code "24") (name "/CAM_SI") (class "Default")
      (node (ref "CAMERA") (pin "6") (pinfunction "6_6") (pintype "passive"))
      (node (ref "U1") (pin "38") (pinfunction "PE8_38") (pintype "bidirectional"))
    )
    (net (code "25") (name "/ENC_A_LEFT") (class "Default")
      (node (ref "U$10") (pin "P$4") (pinfunction "A_P$4") (pintype "bidirectional"))
      (node (ref "U1") (pin "63") (pinfunction "PC6_63") (pintype "bidirectional"))
    )
    (net (code "26") (name "/ENC_A_RIGHT") (class "Default")
      (node (ref "U$1") (pin "P$4") (pinfunction "A_P$4") (pintype "bidirectional"))
      (node (ref "U1") (pin "90") (pinfunction "PB4_90") (pintype "bidirectional"))
    )
    (net (code "27") (name "/ENC_B_LEFT") (class "Default")
      (node (ref "U$10") (pin "P$5") (pinfunction "B_P$5") (pintype "bidirectional"))
      (node (ref "U1") (pin "64") (pinfunction "PC7_64") (pintype "bidirectional"))
    )
    (net (code "28") (name "/ENC_B_RIGHT") (class "Default")
      (node (ref "U$1") (pin "P$5") (pinfunction "B_P$5") (pintype "bidirectional"))
      (node (ref "U1") (pin "91") (pinfunction "PB5_91") (pintype "bidirectional"))
    )
    (net (code "29") (name "/FRONT_GPIO") (class "Default")
      (node (ref "U1") (pin "17") (pinfunction "PC2_17") (pintype "bidirectional"))
      (node (ref "X2") (pin "3") (pinfunction "S_3") (pintype "passive"))
    )
    (net (code "30") (name "/FRONT_SCL") (class "Default")
      (node (ref "U1") (pin "15") (pinfunction "PC0_15") (pintype "bidirectional"))
      (node (ref "X2") (pin "1") (pinfunction "S_1") (pintype "passive"))
    )
    (net (code "31") (name "/FRONT_SDA") (class "Default")
      (node (ref "U1") (pin "16") (pinfunction "PC1_16") (pintype "bidirectional"))
      (node (ref "X2") (pin "2") (pinfunction "S_2") (pintype "passive"))
    )
    (net (code "32") (name "/IR_A") (class "Default")
      (node (ref "Q2") (pin "3") (pinfunction "D_3") (pintype "passive"))
      (node (ref "X2") (pin "15") (pinfunction "S_15") (pintype "passive"))
    )
    (net (code "33") (name "/IR_A_CONTROLL") (class "Default")
      (node (ref "Q2") (pin "1") (pinfunction "G_1") (pintype "passive"))
      (node (ref "R10") (pin "2") (pinfunction "2_2") (pintype "passive"))
      (node (ref "U1") (pin "37") (pinfunction "PE7_37") (pintype "bidirectional"))
    )
    (net (code "34") (name "/IR_A_S") (class "Default")
      (node (ref "R19") (pin "1") (pinfunction "1_1") (pintype "passive"))
      (node (ref "R21") (pin "1") (pinfunction "1_1") (pintype "passive"))
      (node (ref "R23") (pin "1") (pinfunction "1_1") (pintype "passive"))
      (node (ref "R25") (pin "1") (pinfunction "1_1") (pintype "passive"))
      (node (ref "R27") (pin "1") (pinfunction "1_1") (pintype "passive"))
      (node (ref "R29") (pin "1") (pinfunction "1_1") (pintype "passive"))
      (node (ref "R31") (pin "1") (pinfunction "1_1") (pintype "passive"))
      (node (ref "R33") (pin "1") (pinfunction "1_1") (pintype "passive"))
      (node (ref "X3") (pin "4") (pinfunction "S_4") (pintype "passive"))
    )
    (net (code "35") (name "/IR_B") (class "Default")
      (node (ref "Q3") (pin "3") (pinfunction "D_3") (pintype "passive"))
      (node (ref "X2") (pin "16") (pinfunction "S_16") (pintype "passive"))
    )
    (net (code "36") (name "/IR_B_CONTROLL") (class "Default")
      (node (ref "Q3") (pin "1") (pinfunction "G_1") (pintype "passive"))
      (node (ref "R11") (pin "2") (pinfunction "2_2") (pintype "passive"))
      (node (ref "U1") (pin "36") (pinfunction "PB2_36") (pintype "bidirectional"))
    )
    (net (code "37") (name "/IR_B_S") (class "Default")
      (node (ref "U$13") (pin "P$1_COL") (pinfunction "C_P$1_COL") (pintype "passive"))
      (node (ref "U$30") (pin "P$1_COL") (pinfunction "C_P$1_COL") (pintype "passive"))
      (node (ref "U$32") (pin "P$1_COL") (pinfunction "C_P$1_COL") (pintype "passive"))
      (node (ref "X3") (pin "3") (pinfunction "S_3") (pintype "passive"))
    )
    (net (code "38") (name "/IR_FRONT_S") (class "Default")
      (node (ref "R36") (pin "1") (pinfunction "1_1") (pintype "passive"))
      (node (ref "U$29") (pin "P$1_COL") (pinfunction "P$1_P$1_COL") (pintype "bidirectional"))
      (node (ref "X3") (pin "10") (pinfunction "S_10") (pintype "passive"))
    )
    (net (code "39") (name "/IR_LEFT_S") (class "Default")
      (node (ref "R38") (pin "1") (pinfunction "1_1") (pintype "passive"))
      (node (ref "U$31") (pin "P$1_COL") (pinfunction "P$1_P$1_COL") (pintype "bidirectional"))
      (node (ref "X3") (pin "5") (pinfunction "S_5") (pintype "passive"))
    )
    (net (code "40") (name "/IR_REMOTE") (class "Default")
      (node (ref "U$9") (pin "OUT") (pinfunction "OUT_OUT") (pintype "bidirectional"))
      (node (ref "U1") (pin "1") (pinfunction "PE2_1") (pintype "bidirectional"))
    )
    (net (code "41") (name "/IR_RIGHT_S") (class "Default")
      (node (ref "R34") (pin "1") (pinfunction "1_1") (pintype "passive"))
      (node (ref "U$12") (pin "P$1_COL") (pinfunction "P$1_P$1_COL") (pintype "bidirectional"))
      (node (ref "X3") (pin "15") (pinfunction "S_15") (pintype "passive"))
    )
    (net (code "42") (name "/KEY") (class "Default")
      (node (ref "RUN") (pin "3") (pinfunction "3_3") (pintype "passive"))
      (node (ref "U1") (pin "2") (pinfunction "PE3_2") (pintype "bidirectional"))
    )
    (net (code "43") (name "/LED") (class "Default")
      (node (ref "R3") (pin "2") (pinfunction "2_2") (pintype "passive"))
      (node (ref "U1") (pin "67") (pinfunction "PA8_67") (pintype "bidirectional"))
    )
    (net (code "44") (name "/LED_BACK") (class "Default")
      (node (ref "Q4") (pin "1") (pinfunction "G_1") (pintype "passive"))
      (node (ref "R12") (pin "2") (pinfunction "2_2") (pintype "passive"))
      (node (ref "U1") (pin "60") (pinfunction "PD13_60") (pintype "bidirectional"))
    )
    (net (code "45") (name "/MOTOR_ENABLE") (class "Default")
      (node (ref "IC2") (pin "25") (pinfunction "EN/~{D4}_25") (pintype "input"))
      (node (ref "IC2") (pin "3") (pinfunction "EN/~{D2}_3") (pintype "input"))
      (node (ref "R7") (pin "2") (pinfunction "2_2") (pintype "passive"))
      (node (ref "U1") (pin "81") (pinfunction "PD0_81") (pintype "bidirectional"))
    )
    (net (code "46") (name "/NC") (class "Default")
      (node (ref "CAMERA") (pin "4") (pinfunction "4_4") (pintype "passive"))
    )
    (net (code "47") (name "/PWM_A_LEFT") (class "Default")
      (node (ref "IC2") (pin "43") (pinfunction "IN1_43") (pintype "input"))
      (node (ref "U1") (pin "42") (pinfunction "PE12_42") (pintype "bidirectional"))
    )
    (net (code "48") (name "/PWM_A_RIGHT") (class "Default")
      (node (ref "IC2") (pin "21") (pinfunction "IN3_21") (pintype "input"))
      (node (ref "U1") (pin "40") (pinfunction "PE10_40") (pintype "bidirectional"))
    )
    (net (code "49") (name "/PWM_B_LEFT") (class "Default")
      (node (ref "IC2") (pin "42") (pinfunction "IN2_42") (pintype "input"))
      (node (ref "U1") (pin "43") (pinfunction "PE13_43") (pintype "bidirectional"))
    )
    (net (code "50") (name "/PWM_B_RIGHT") (class "Default")
      (node (ref "IC2") (pin "20") (pinfunction "IN4_20") (pintype "input"))
      (node (ref "U1") (pin "41") (pinfunction "PE11_41") (pintype "bidirectional"))
    )
    (net (code "51") (name "/RESET") (class "Default")
      (node (ref "C3") (pin "1") (pinfunction "1_1") (pintype "passive"))
      (node (ref "R1") (pin "1") (pinfunction "1_1") (pintype "passive"))
      (node (ref "RESET") (pin "3") (pinfunction "3_3") (pintype "passive"))
      (node (ref "U1") (pin "14") (pinfunction "NRST_14") (pintype "bidirectional"))
    )
    (net (code "52") (name "/SCL") (class "Default")
      (node (ref "R5") (pin "1") (pinfunction "1_1") (pintype "passive"))
      (node (ref "U$2") (pin "P$2") (pinfunction "SCL/SPC_P$2") (pintype "bidirectional"))
      (node (ref "U1") (pin "83") (pinfunction "PD2_83") (pintype "bidirectional"))
      (node (ref "U2") (pin "6") (pinfunction "SCL_6") (pintype "bidirectional"))
    )
    (net (code "53") (name "/SDA") (class "Default")
      (node (ref "R4") (pin "1") (pinfunction "1_1") (pintype "passive"))
      (node (ref "U$2") (pin "P$3") (pinfunction "SDA/SDI_P$3") (pintype "bidirectional"))
      (node (ref "U1") (pin "82") (pinfunction "PD1_82") (pintype "bidirectional"))
      (node (ref "U2") (pin "5") (pinfunction "SDA_5") (pintype "bidirectional"))
    )
    (net (code "54") (name "/USART1_RX") (class "Default")
      (node (ref "U1") (pin "69") (pinfunction "PA10_69") (pintype "bidirectional"))
      (node (ref "USART") (pin "3") (pinfunction "3_3") (pintype "passive"))
    )
    (net (code "55") (name "/USART1_TX") (class "Default")
      (node (ref "U1") (pin "68") (pinfunction "PA9_68") (pintype "bidirectional"))
      (node (ref "USART") (pin "2") (pinfunction "2_2") (pintype "passive"))
    )
    (net (code "56") (name "/USBDM") (class "Default")
      (node (ref "U1") (pin "70") (pinfunction "PA_11_70") (pintype "bidirectional"))
      (node (ref "X4") (pin "2") (pinfunction "2_2") (pintype "passive"))
    )
    (net (code "57") (name "/USBDP") (class "Default")
      (node (ref "U1") (pin "71") (pinfunction "PA12_71") (pintype "bidirectional"))
      (node (ref "X4") (pin "3") (pinfunction "3_3") (pintype "passive"))
    )
    (net (code "58") (name "/VBAT") (class "Default")
      (node (ref "U1") (pin "6") (pinfunction "VBAT_6") (pintype "power_in"))
    )
    (net (code "59") (name "GND") (class "Default")
      (node (ref "BAT") (pin "1") (pinfunction "1_1") (pintype "passive"))
      (node (ref "C1") (pin "2") (pinfunction "2_2") (pintype "passive"))
      (node (ref "C10") (pin "2") (pinfunction "2_2") (pintype "passive"))
      (node (ref "C11") (pin "2") (pinfunction "2_2") (pintype "passive"))
      (node (ref "C12") (pin "2") (pinfunction "2_2") (pintype "passive"))
      (node (ref "C13") (pin "2") (pinfunction "2_2") (pintype "passive"))
      (node (ref "C14") (pin "2") (pinfunction "2_2") (pintype "passive"))
      (node (ref "C15") (pin "2") (pinfunction "2_2") (pintype "passive"))
      (node (ref "C16") (pin "2") (pinfunction "2_2") (pintype "passive"))
      (node (ref "C19") (pin "2") (pinfunction "2_2") (pintype "passive"))
      (node (ref "C2") (pin "2") (pinfunction "2_2") (pintype "passive"))
      (node (ref "C20") (pin "-") (pinfunction "-_-") (pintype "passive"))
      (node (ref "C21") (pin "-") (pinfunction "-_-") (pintype "passive"))
      (node (ref "C22") (pin "-") (pinfunction "-_-") (pintype "passive"))
      (node (ref "C23") (pin "2") (pinfunction "2_2") (pintype "passive"))
      (node (ref "C24") (pin "-") (pinfunction "-_-") (pintype "passive"))
      (node (ref "C25") (pin "2") (pinfunction "2_2") (pintype "passive"))
      (node (ref "C26") (pin "2") (pinfunction "2_2") (pintype "passive"))
      (node (ref "C3") (pin "2") (pinfunction "2_2") (pintype "passive"))
      (node (ref "C4") (pin "2") (pinfunction "2_2") (pintype "passive"))
      (node (ref "C5") (pin "1") (pinfunction "1_1") (pintype "passive"))
      (node (ref "C6") (pin "2") (pinfunction "2_2") (pintype "passive"))
      (node (ref "C7") (pin "2") (pinfunction "2_2") (pintype "passive"))
      (node (ref "C8") (pin "2") (pinfunction "2_2") (pintype "passive"))
      (node (ref "C9") (pin "2") (pinfunction "2_2") (pintype "passive"))
      (node (ref "CAMERA") (pin "2") (pinfunction "2_2") (pintype "passive"))
      (node (ref "IC1") (pin "2") (pinfunction "GND_2") (pintype "passive"))
      (node (ref "IC2") (pin "1") (pinfunction "D1_1") (pintype "input"))
      (node (ref "IC2") (pin "10") (pinfunction "PGNDA_10") (pintype "power_in"))
      (node (ref "IC2") (pin "11") (pinfunction "PGNDA_11") (pintype "power_in"))
      (node (ref "IC2") (pin "12") (pinfunction "PGNDB_12") (pintype "power_in"))
      (node (ref "IC2") (pin "13") (pinfunction "PGNDB_13") (pintype "power_in"))
      (node (ref "IC2") (pin "23") (pinfunction "D3_23") (pintype "input"))
      (node (ref "IC2") (pin "32") (pinfunction "PGNDB_32") (pintype "power_in"))
      (node (ref "IC2") (pin "33") (pinfunction "PGNDB_33") (pintype "power_in"))
      (node (ref "IC2") (pin "34") (pinfunction "PGNDA_34") (pintype "power_in"))
      (node (ref "IC2") (pin "35") (pinfunction "PGNDA_35") (pintype "power_in"))
      (node (ref "IC2") (pin "EH@1") (pinfunction "EH_EH@1") (pintype "passive"))
      (node (ref "IC2") (pin "EH@2") (pinfunction "EH_EH@2") (pintype "passive"))
      (node (ref "IC2") (pin "EH@3") (pinfunction "EH_EH@3") (pintype "passive"))
      (node (ref "LED1") (pin "C") (pinfunction "C_C") (pintype "passive"))
      (node (ref "LED2") (pin "C") (pinfunction "C_C") (pintype "passive"))
      (node (ref "Q2") (pin "2") (pinfunction "S_2") (pintype "passive"))
      (node (ref "Q3") (pin "2") (pinfunction "S_2") (pintype "passive"))
      (node (ref "Q4") (pin "2") (pinfunction "S_2") (pintype "passive"))
      (node (ref "R10") (pin "1") (pinfunction "1_1") (pintype "passive"))
      (node (ref "R11") (pin "1") (pinfunction "1_1") (pintype "passive"))
      (node (ref "R12") (pin "1") (pinfunction "1_1") (pintype "passive"))
      (node (ref "R2") (pin "1") (pinfunction "1_1") (pintype "passive"))
      (node (ref "R7") (pin "1") (pinfunction "1_1") (pintype "passive"))
      (node (ref "R8") (pin "1") (pinfunction "1_1") (pintype "passive"))
      (node (ref "R9") (pin "2") (pinfunction "2_2") (pintype "passive"))
      (node (ref "RESET") (pin "1") (pinfunction "1_1") (pintype "passive"))
      (node (ref "RUN") (pin "1") (pinfunction "1_1") (pintype "passive"))
      (node (ref "U$1") (pin "P$6") (pinfunction "GND_P$6") (pintype "bidirectional"))
      (node (ref "U$10") (pin "P$6") (pinfunction "GND_P$6") (pintype "bidirectional"))
      (node (ref "U$11") (pin "P$1") (pinfunction "E_P$1") (pintype "bidirectional"))
      (node (ref "U$12") (pin "P$2_EM") (pinfunction "P$2_P$2_EM") (pintype "bidirectional"))
      (node (ref "U$12") (pin "P$3-NC") (pinfunction "P$2_P$3-NC") (pintype "bidirectional"))
      (node (ref "U$14") (pin "P$1") (pinfunction "E_P$1") (pintype "bidirectional"))
      (node (ref "U$15") (pin "P$1") (pinfunction "E_P$1") (pintype "bidirectional"))
      (node (ref "U$16") (pin "P$1") (pinfunction "E_P$1") (pintype "bidirectional"))
      (node (ref "U$17") (pin "P$1") (pinfunction "E_P$1") (pintype "bidirectional"))
      (node (ref "U$18") (pin "P$1") (pinfunction "E_P$1") (pintype "bidirectional"))
      (node (ref "U$19") (pin "P$1") (pinfunction "E_P$1") (pintype "bidirectional"))
      (node (ref "U$2") (pin "P$10") (pinfunction "RES2_P$10") (pintype "bidirectional"))
      (node (ref "U$2") (pin "P$11") (pinfunction "RES3_P$11") (pintype "bidirectional"))
      (node (ref "U$2") (pin "P$12") (pinfunction "GND_P$12") (pintype "power_in"))
      (node (ref "U$2") (pin "P$13") (pinfunction "GND_P$13") (pintype "power_in"))
      (node (ref "U$2") (pin "P$15") (pinfunction "RES4_P$15") (pintype "bidirectional"))
      (node (ref "U$2") (pin "P$4") (pinfunction "SDO_P$4") (pintype "bidirectional"))
      (node (ref "U$2") (pin "P$8") (pinfunction "DEN_P$8") (pintype "bidirectional"))
      (node (ref "U$2") (pin "P$9") (pinfunction "RES1_P$9") (pintype "bidirectional"))
      (node (ref "U$20") (pin "P$1") (pinfunction "E_P$1") (pintype "bidirectional"))
      (node (ref "U$29") (pin "P$2_EM") (pinfunction "P$2_P$2_EM") (pintype "bidirectional"))
      (node (ref "U$29") (pin "P$3-NC") (pinfunction "P$2_P$3-NC") (pintype "bidirectional"))
      (node (ref "U$31") (pin "P$2_EM") (pinfunction "P$2_P$2_EM") (pintype "bidirectional"))
      (node (ref "U$31") (pin "P$3-NC") (pinfunction "P$2_P$3-NC") (pintype "bidirectional"))
      (node (ref "U$9") (pin "GND") (pinfunction "GND_GND") (pintype "bidirectional"))
      (node (ref "U1") (pin "10") (pinfunction "VSS_2_10") (pintype "passive"))
      (node (ref "U1") (pin "19") (pinfunction "VSSA_19") (pintype "passive"))
      (node (ref "U1") (pin "26") (pinfunction "VSS_26") (pintype "passive"))
      (node (ref "U1") (pin "49") (pinfunction "VSS_4_49") (pintype "power_in"))
      (node (ref "U1") (pin "74") (pinfunction "VSS_2_74") (pintype "passive"))
      (node (ref "U1") (pin "99") (pinfunction "VSS_99") (pintype "passive"))
      (node (ref "U2") (pin "1") (pinfunction "A0_1") (pintype "bidirectional"))
      (node (ref "U2") (pin "2") (pinfunction "A1_2") (pintype "bidirectional"))
      (node (ref "U2") (pin "3") (pinfunction "A2_3") (pintype "bidirectional"))
      (node (ref "U2") (pin "4") (pinfunction "VSS_4") (pintype "power_in"))
      (node (ref "USART") (pin "1") (pinfunction "1_1") (pintype "passive"))
      (node (ref "X2") (pin "18") (pinfunction "S_18") (pintype "passive"))
      (node (ref "X3") (pin "1") (pinfunction "S_1") (pintype "passive"))
      (node (ref "X4") (pin "5") (pinfunction "5_5") (pintype "passive"))
      (node (ref "X4") (pin "M1") (pinfunction "S1_M1") (pintype "passive"))
      (node (ref "X4") (pin "M2") (pinfunction "S2_M2") (pintype "passive"))
      (node (ref "X4") (pin "M3") (pinfunction "S3_M3") (pintype "passive"))
      (node (ref "X4") (pin "M4") (pinfunction "S4_M4") (pintype "passive"))
    )
    (net (code "60") (name "Net-(D1-PadA)") (class "Default")
      (node (ref "D1") (pin "A") (pinfunction "A_A") (pintype "passive"))
      (node (ref "X4") (pin "1") (pinfunction "1_1") (pintype "passive"))
    )
    (net (code "61") (name "Net-(IC2-CCPA)") (class "Default")
      (node (ref "C17") (pin "2") (pinfunction "2_2") (pintype "passive"))
      (node (ref "IC2") (pin "41") (pinfunction "CCPA_41") (pintype "output"))
    )
    (net (code "62") (name "Net-(IC2-CCPB)") (class "Default")
      (node (ref "C18") (pin "1") (pinfunction "1_1") (pintype "passive"))
      (node (ref "IC2") (pin "19") (pinfunction "CCPB_19") (pintype "output"))
    )
    (net (code "63") (name "Net-(IC2-FBA)") (class "Default")
      (node (ref "IC2") (pin "2") (pinfunction "FBA_2") (pintype "output"))
      (node (ref "R8") (pin "2") (pinfunction "2_2") (pintype "passive"))
    )
    (net (code "64") (name "Net-(IC2-FBB)") (class "Default")
      (node (ref "IC2") (pin "24") (pinfunction "FBB_24") (pintype "output"))
      (node (ref "R9") (pin "1") (pinfunction "1_1") (pintype "passive"))
    )
    (net (code "65") (name "Net-(IC2-OUT1-Pad7)") (class "Default")
      (node (ref "IC2") (pin "7") (pinfunction "OUT1_7") (pintype "output"))
      (node (ref "IC2") (pin "8") (pinfunction "OUT1_8") (pintype "passive"))
      (node (ref "IC2") (pin "9") (pinfunction "OUT1_9") (pintype "passive"))
      (node (ref "U$10") (pin "P$1") (pinfunction "P$1_P$1") (pintype "bidirectional"))
    )
    (net (code "66") (name "Net-(IC2-OUT2-Pad36)") (class "Default")
      (node (ref "IC2") (pin "36") (pinfunction "OUT2_36") (pintype "output"))
      (node (ref "IC2") (pin "37") (pinfunction "OUT2_37") (pintype "passive"))
      (node (ref "IC2") (pin "38") (pinfunction "OUT2_38") (pintype "passive"))
      (node (ref "U$10") (pin "P$2") (pinfunction "P$2_P$2") (pintype "bidirectional"))
    )
    (net (code "67") (name "Net-(IC2-OUT3-Pad29)") (class "Default")
      (node (ref "IC2") (pin "29") (pinfunction "OUT3_29") (pintype "output"))
      (node (ref "IC2") (pin "30") (pinfunction "OUT3_30") (pintype "passive"))
      (node (ref "IC2") (pin "31") (pinfunction "OUT3_31") (pintype "passive"))
      (node (ref "U$1") (pin "P$1") (pinfunction "P$1_P$1") (pintype "bidirectional"))
    )
    (net (code "68") (name "Net-(IC2-OUT4-Pad14)") (class "Default")
      (node (ref "IC2") (pin "14") (pinfunction "OUT4_14") (pintype "output"))
      (node (ref "IC2") (pin "15") (pinfunction "OUT4_15") (pintype "passive"))
      (node (ref "IC2") (pin "16") (pinfunction "OUT4_16") (pintype "passive"))
      (node (ref "U$1") (pin "P$2") (pinfunction "P$2_P$2") (pintype "bidirectional"))
    )
    (net (code "69") (name "Net-(LED1-PadA)") (class "Default")
      (node (ref "LED1") (pin "A") (pinfunction "A_A") (pintype "passive"))
      (node (ref "R3") (pin "1") (pinfunction "1_1") (pintype "passive"))
    )
    (net (code "70") (name "Net-(LED2-PadA)") (class "Default")
      (node (ref "LED2") (pin "A") (pinfunction "A_A") (pintype "passive"))
      (node (ref "R6") (pin "1") (pinfunction "1_1") (pintype "passive"))
    )
    (net (code "71") (name "Net-(LED3-PadA)") (class "Default")
      (node (ref "LED3") (pin "A") (pinfunction "A_A") (pintype "passive"))
      (node (ref "R13") (pin "1") (pinfunction "1_1") (pintype "passive"))
    )
    (net (code "72") (name "Net-(LED4-PadA)") (class "Default")
      (node (ref "LED4") (pin "A") (pinfunction "A_A") (pintype "passive"))
      (node (ref "R14") (pin "1") (pinfunction "1_1") (pintype "passive"))
    )
    (net (code "73") (name "Net-(LED5-PadA)") (class "Default")
      (node (ref "LED5") (pin "A") (pinfunction "A_A") (pintype "passive"))
      (node (ref "R15") (pin "1") (pinfunction "1_1") (pintype "passive"))
    )
    (net (code "74") (name "Net-(LED6-PadA)") (class "Default")
      (node (ref "LED6") (pin "A") (pinfunction "A_A") (pintype "passive"))
      (node (ref "R16") (pin "1") (pinfunction "1_1") (pintype "passive"))
    )
    (net (code "75") (name "Net-(LED7-PadC)") (class "Default")
      (node (ref "LED7") (pin "C") (pinfunction "C_C") (pintype "passive"))
      (node (ref "R19") (pin "2") (pinfunction "2_2") (pintype "passive"))
    )
    (net (code "76") (name "Net-(LED8-PadC)") (class "Default")
      (node (ref "LED8") (pin "C") (pinfunction "C_C") (pintype "passive"))
      (node (ref "R21") (pin "2") (pinfunction "2_2") (pintype "passive"))
    )
    (net (code "77") (name "Net-(LED9-PadC)") (class "Default")
      (node (ref "LED9") (pin "C") (pinfunction "C_C") (pintype "passive"))
      (node (ref "R23") (pin "2") (pinfunction "2_2") (pintype "passive"))
    )
    (net (code "78") (name "Net-(LED10-PadC)") (class "Default")
      (node (ref "LED10") (pin "C") (pinfunction "C_C") (pintype "passive"))
      (node (ref "R25") (pin "2") (pinfunction "2_2") (pintype "passive"))
    )
    (net (code "79") (name "Net-(LED11-PadC)") (class "Default")
      (node (ref "LED11") (pin "C") (pinfunction "C_C") (pintype "passive"))
      (node (ref "R27") (pin "2") (pinfunction "2_2") (pintype "passive"))
    )
    (net (code "80") (name "Net-(LED12-PadC)") (class "Default")
      (node (ref "LED12") (pin "C") (pinfunction "C_C") (pintype "passive"))
      (node (ref "R29") (pin "2") (pinfunction "2_2") (pintype "passive"))
    )
    (net (code "81") (name "Net-(LED13-PadC)") (class "Default")
      (node (ref "LED13") (pin "C") (pinfunction "C_C") (pintype "passive"))
      (node (ref "R31") (pin "2") (pinfunction "2_2") (pintype "passive"))
    )
    (net (code "82") (name "Net-(LED14-PadC)") (class "Default")
      (node (ref "LED14") (pin "C") (pinfunction "C_C") (pintype "passive"))
      (node (ref "R33") (pin "2") (pinfunction "2_2") (pintype "passive"))
    )
    (net (code "83") (name "Net-(Q1-2)") (class "Default")
      (node (ref "C2") (pin "1") (pinfunction "1_1") (pintype "passive"))
      (node (ref "Q1") (pin "3") (pinfunction "2_3") (pintype "passive"))
      (node (ref "U1") (pin "12") (pinfunction "PH0_12") (pintype "bidirectional"))
    )
    (net (code "84") (name "Net-(Q4-D)") (class "Default")
      (node (ref "LED3") (pin "C") (pinfunction "C_C") (pintype "passive"))
      (node (ref "LED4") (pin "C") (pinfunction "C_C") (pintype "passive"))
      (node (ref "LED5") (pin "C") (pinfunction "C_C") (pintype "passive"))
      (node (ref "LED6") (pin "C") (pinfunction "C_C") (pintype "passive"))
      (node (ref "Q4") (pin "3") (pinfunction "D_3") (pintype "passive"))
    )
    (net (code "85") (name "Net-(R35-Pad1)") (class "Default")
      (node (ref "R35") (pin "1") (pinfunction "1_1") (pintype "passive"))
      (node (ref "U$13") (pin "P$2_EM") (pinfunction "A_P$2_EM") (pintype "passive"))
      (node (ref "U$13") (pin "P$3-NC") (pinfunction "A_P$3-NC") (pintype "passive"))
    )
    (net (code "86") (name "Net-(R37-Pad1)") (class "Default")
      (node (ref "R37") (pin "1") (pinfunction "1_1") (pintype "passive"))
      (node (ref "U$30") (pin "P$2_EM") (pinfunction "A_P$2_EM") (pintype "passive"))
      (node (ref "U$30") (pin "P$3-NC") (pinfunction "A_P$3-NC") (pintype "passive"))
    )
    (net (code "87") (name "Net-(R39-Pad1)") (class "Default")
      (node (ref "R39") (pin "1") (pinfunction "1_1") (pintype "passive"))
      (node (ref "U$32") (pin "P$2_EM") (pinfunction "A_P$2_EM") (pintype "passive"))
      (node (ref "U$32") (pin "P$3-NC") (pinfunction "A_P$3-NC") (pintype "passive"))
    )
    (net (code "88") (name "Net-(U$2-CAP)") (class "Default")
      (node (ref "C14") (pin "1") (pinfunction "1_1") (pintype "passive"))
      (node (ref "U$2") (pin "P$14") (pinfunction "CAP_P$14") (pintype "bidirectional"))
    )
    (net (code "89") (name "Net-(U$9-V+)") (class "Default")
      (node (ref "C25") (pin "1") (pinfunction "1_1") (pintype "passive"))
      (node (ref "R17") (pin "1") (pinfunction "1_1") (pintype "passive"))
      (node (ref "U$9") (pin "VCC") (pinfunction "V+_VCC") (pintype "bidirectional"))
    )
    (net (code "90") (name "Net-(U1A-PH1)") (class "Default")
      (node (ref "C1") (pin "1") (pinfunction "1_1") (pintype "passive"))
      (node (ref "Q1") (pin "1") (pinfunction "1_1") (pintype "passive"))
      (node (ref "U1") (pin "13") (pinfunction "PH1_13") (pintype "bidirectional"))
    )
    (net (code "91") (name "Net-(U1A-VCAP_1)") (class "Default")
      (node (ref "C4") (pin "1") (pinfunction "1_1") (pintype "passive"))
      (node (ref "U1") (pin "48") (pinfunction "VCAP_1_48") (pintype "power_in"))
    )
    (net (code "92") (name "Net-(U1B-VCAP_2)") (class "Default")
      (node (ref "C5") (pin "2") (pinfunction "2_2") (pintype "passive"))
      (node (ref "U1") (pin "73") (pinfunction "VCAP_2_73") (pintype "power_in"))
    )
    (net (code "93") (name "VCC") (class "Default")
      (node (ref "BAT") (pin "2") (pinfunction "2_2") (pintype "passive"))
      (node (ref "C10") (pin "1") (pinfunction "1_1") (pintype "passive"))
      (node (ref "C11") (pin "1") (pinfunction "1_1") (pintype "passive"))
      (node (ref "C17") (pin "1") (pinfunction "1_1") (pintype "passive"))
      (node (ref "C18") (pin "2") (pinfunction "2_2") (pintype "passive"))
      (node (ref "C19") (pin "1") (pinfunction "1_1") (pintype "passive"))
      (node (ref "C20") (pin "+") (pinfunction "+_+") (pintype "passive"))
      (node (ref "C21") (pin "+") (pinfunction "+_+") (pintype "passive"))
      (node (ref "C23") (pin "1") (pinfunction "1_1") (pintype "passive"))
      (node (ref "D1") (pin "C") (pinfunction "C_C") (pintype "passive"))
      (node (ref "IC1") (pin "1") (pinfunction "VI_1") (pintype "input"))
      (node (ref "IC2") (pin "17") (pinfunction "VPWRB_17") (pintype "input"))
      (node (ref "IC2") (pin "18") (pinfunction "VPWRB_18") (pintype "input"))
      (node (ref "IC2") (pin "26") (pinfunction "VPWRB_26") (pintype "input"))
      (node (ref "IC2") (pin "27") (pinfunction "VPWRB_27") (pintype "input"))
      (node (ref "IC2") (pin "28") (pinfunction "VPWRB_28") (pintype "input"))
      (node (ref "IC2") (pin "39") (pinfunction "VPWRA_39") (pintype "input"))
      (node (ref "IC2") (pin "4") (pinfunction "VPWRA_4") (pintype "input"))
      (node (ref "IC2") (pin "40") (pinfunction "VPWRA_40") (pintype "input"))
      (node (ref "IC2") (pin "5") (pinfunction "VPWRA_5") (pintype "input"))
      (node (ref "IC2") (pin "6") (pinfunction "VPWRA_6") (pintype "input"))
    )
    (net (code "94") (name "unconnected-(IC2-~{SFA}-Pad44)") (class "Default")
      (node (ref "IC2") (pin "44") (pinfunction "~{SFA}_44") (pintype "open_collector"))
    )
    (net (code "95") (name "unconnected-(IC2-~{SFB}-Pad22)") (class "Default")
      (node (ref "IC2") (pin "22") (pinfunction "~{SFB}_22") (pintype "open_collector"))
    )
    (net (code "96") (name "unconnected-(RESET-Pad2)") (class "Default")
      (node (ref "RESET") (pin "2") (pinfunction "2_2") (pintype "passive"))
    )
    (net (code "97") (name "unconnected-(RESET-Pad4)") (class "Default")
      (node (ref "RESET") (pin "4") (pinfunction "4_4") (pintype "passive"))
    )
    (net (code "98") (name "unconnected-(RUN-Pad2)") (class "Default")
      (node (ref "RUN") (pin "2") (pinfunction "2_2") (pintype "passive"))
    )
    (net (code "99") (name "unconnected-(RUN-Pad4)") (class "Default")
      (node (ref "RUN") (pin "4") (pinfunction "4_4") (pintype "passive"))
    )
    (net (code "100") (name "unconnected-(U$2-DRDY{slash}INT2-PadP$6)") (class "Default")
      (node (ref "U$2") (pin "P$6") (pinfunction "DRDY/INT2_P$6") (pintype "bidirectional"))
    )
    (net (code "101") (name "unconnected-(U$2-INT1-PadP$7)") (class "Default")
      (node (ref "U$2") (pin "P$7") (pinfunction "INT1_P$7") (pintype "bidirectional"))
    )
    (net (code "102") (name "unconnected-(U1A-PB10-Pad46)") (class "Default")
      (node (ref "U1") (pin "46") (pinfunction "PB10_46") (pintype "bidirectional"))
    )
    (net (code "103") (name "unconnected-(U1A-PB11-Pad47)") (class "Default")
      (node (ref "U1") (pin "47") (pinfunction "PB11_47") (pintype "bidirectional"))
    )
    (net (code "104") (name "unconnected-(U1A-PC3-Pad18)") (class "Default")
      (node (ref "U1") (pin "18") (pinfunction "PC3_18") (pintype "bidirectional"))
    )
    (net (code "105") (name "unconnected-(U1A-PC13-Pad7)") (class "Default")
      (node (ref "U1") (pin "7") (pinfunction "PC13_7") (pintype "bidirectional"))
    )
    (net (code "106") (name "unconnected-(U1A-PC14-Pad8)") (class "Default")
      (node (ref "U1") (pin "8") (pinfunction "PC14_8") (pintype "bidirectional"))
    )
    (net (code "107") (name "unconnected-(U1A-PC15-Pad9)") (class "Default")
      (node (ref "U1") (pin "9") (pinfunction "PC15_9") (pintype "bidirectional"))
    )
    (net (code "108") (name "unconnected-(U1A-PE4-Pad3)") (class "Default")
      (node (ref "U1") (pin "3") (pinfunction "PE4_3") (pintype "bidirectional"))
    )
    (net (code "109") (name "unconnected-(U1A-PE5-Pad4)") (class "Default")
      (node (ref "U1") (pin "4") (pinfunction "PE5_4") (pintype "bidirectional"))
    )
    (net (code "110") (name "unconnected-(U1A-PE6-Pad5)") (class "Default")
      (node (ref "U1") (pin "5") (pinfunction "PE6_5") (pintype "bidirectional"))
    )
    (net (code "111") (name "unconnected-(U1A-PE14-Pad44)") (class "Default")
      (node (ref "U1") (pin "44") (pinfunction "PE14_44") (pintype "bidirectional"))
    )
    (net (code "112") (name "unconnected-(U1A-PE15-Pad45)") (class "Default")
      (node (ref "U1") (pin "45") (pinfunction "PE15_45") (pintype "bidirectional"))
    )
    (net (code "113") (name "unconnected-(U1B-PA13-Pad72)") (class "Default")
      (node (ref "U1") (pin "72") (pinfunction "PA13_72") (pintype "bidirectional"))
    )
    (net (code "114") (name "unconnected-(U1B-PA14-Pad76)") (class "Default")
      (node (ref "U1") (pin "76") (pinfunction "PA14_76") (pintype "bidirectional"))
    )
    (net (code "115") (name "unconnected-(U1B-PA15-Pad77)") (class "Default")
      (node (ref "U1") (pin "77") (pinfunction "PA15_77") (pintype "bidirectional"))
    )
    (net (code "116") (name "unconnected-(U1B-PB3-Pad89)") (class "Default")
      (node (ref "U1") (pin "89") (pinfunction "PB3_89") (pintype "bidirectional"))
    )
    (net (code "117") (name "unconnected-(U1B-PB6-Pad92)") (class "Default")
      (node (ref "U1") (pin "92") (pinfunction "PB6_92") (pintype "bidirectional"))
    )
    (net (code "118") (name "unconnected-(U1B-PB7-Pad93)") (class "Default")
      (node (ref "U1") (pin "93") (pinfunction "PB7_93") (pintype "bidirectional"))
    )
    (net (code "119") (name "unconnected-(U1B-PB8-Pad95)") (class "Default")
      (node (ref "U1") (pin "95") (pinfunction "PB8_95") (pintype "bidirectional"))
    )
    (net (code "120") (name "unconnected-(U1B-PB9-Pad96)") (class "Default")
      (node (ref "U1") (pin "96") (pinfunction "PB9_96") (pintype "bidirectional"))
    )
    (net (code "121") (name "unconnected-(U1B-PB12-Pad51)") (class "Default")
      (node (ref "U1") (pin "51") (pinfunction "PB12_51") (pintype "bidirectional"))
    )
    (net (code "122") (name "unconnected-(U1B-PB13-Pad52)") (class "Default")
      (node (ref "U1") (pin "52") (pinfunction "PB13_52") (pintype "bidirectional"))
    )
    (net (code "123") (name "unconnected-(U1B-PB14-Pad53)") (class "Default")
      (node (ref "U1") (pin "53") (pinfunction "PB14_53") (pintype "bidirectional"))
    )
    (net (code "124") (name "unconnected-(U1B-PB15-Pad54)") (class "Default")
      (node (ref "U1") (pin "54") (pinfunction "PB15_54") (pintype "bidirectional"))
    )
    (net (code "125") (name "unconnected-(U1B-PC8-Pad65)") (class "Default")
      (node (ref "U1") (pin "65") (pinfunction "PC8_65") (pintype "bidirectional"))
    )
    (net (code "126") (name "unconnected-(U1B-PC9-Pad66)") (class "Default")
      (node (ref "U1") (pin "66") (pinfunction "PC9_66") (pintype "bidirectional"))
    )
    (net (code "127") (name "unconnected-(U1B-PC10-Pad78)") (class "Default")
      (node (ref "U1") (pin "78") (pinfunction "PC10_78") (pintype "bidirectional"))
    )
    (net (code "128") (name "unconnected-(U1B-PC11-Pad79)") (class "Default")
      (node (ref "U1") (pin "79") (pinfunction "PC11_79") (pintype "bidirectional"))
    )
    (net (code "129") (name "unconnected-(U1B-PC12-Pad80)") (class "Default")
      (node (ref "U1") (pin "80") (pinfunction "PC12_80") (pintype "bidirectional"))
    )
    (net (code "130") (name "unconnected-(U1B-PD3-Pad84)") (class "Default")
      (node (ref "U1") (pin "84") (pinfunction "PD3_84") (pintype "bidirectional"))
    )
    (net (code "131") (name "unconnected-(U1B-PD4-Pad85)") (class "Default")
      (node (ref "U1") (pin "85") (pinfunction "PD4_85") (pintype "bidirectional"))
    )
    (net (code "132") (name "unconnected-(U1B-PD5-Pad86)") (class "Default")
      (node (ref "U1") (pin "86") (pinfunction "PD5_86") (pintype "bidirectional"))
    )
    (net (code "133") (name "unconnected-(U1B-PD6-Pad87)") (class "Default")
      (node (ref "U1") (pin "87") (pinfunction "PD6_87") (pintype "bidirectional"))
    )
    (net (code "134") (name "unconnected-(U1B-PD7-Pad88)") (class "Default")
      (node (ref "U1") (pin "88") (pinfunction "PD7_88") (pintype "bidirectional"))
    )
    (net (code "135") (name "unconnected-(U1B-PD8-Pad55)") (class "Default")
      (node (ref "U1") (pin "55") (pinfunction "PD8_55") (pintype "bidirectional"))
    )
    (net (code "136") (name "unconnected-(U1B-PD9-Pad56)") (class "Default")
      (node (ref "U1") (pin "56") (pinfunction "PD9_56") (pintype "bidirectional"))
    )
    (net (code "137") (name "unconnected-(U1B-PD10-Pad57)") (class "Default")
      (node (ref "U1") (pin "57") (pinfunction "PD10_57") (pintype "bidirectional"))
    )
    (net (code "138") (name "unconnected-(U1B-PD11-Pad58)") (class "Default")
      (node (ref "U1") (pin "58") (pinfunction "PD11_58") (pintype "bidirectional"))
    )
    (net (code "139") (name "unconnected-(U1B-PD12-Pad59)") (class "Default")
      (node (ref "U1") (pin "59") (pinfunction "PD12_59") (pintype "bidirectional"))
    )
    (net (code "140") (name "unconnected-(U1B-PD14-Pad61)") (class "Default")
      (node (ref "U1") (pin "61") (pinfunction "PD14_61") (pintype "bidirectional"))
    )
    (net (code "141") (name "unconnected-(U1B-PD15-Pad62)") (class "Default")
      (node (ref "U1") (pin "62") (pinfunction "PD15_62") (pintype "bidirectional"))
    )
    (net (code "142") (name "unconnected-(U1B-PE0-Pad97)") (class "Default")
      (node (ref "U1") (pin "97") (pinfunction "PE0_97") (pintype "bidirectional"))
    )
    (net (code "143") (name "unconnected-(U1B-PE1-Pad98)") (class "Default")
      (node (ref "U1") (pin "98") (pinfunction "PE1_98") (pintype "bidirectional"))
    )
    (net (code "144") (name "unconnected-(X3H-S-Pad16)") (class "Default")
      (node (ref "X3") (pin "16") (pinfunction "S_16") (pintype "passive"))
    )
    (net (code "145") (name "unconnected-(X3I-S-Pad17)") (class "Default")
      (node (ref "X3") (pin "17") (pinfunction "S_17") (pintype "passive"))
    )
    (net (code "146") (name "unconnected-(X3J-S-Pad18)") (class "Default")
      (node (ref "X3") (pin "18") (pinfunction "S_18") (pintype "passive"))
    )
    (net (code "147") (name "unconnected-(X4-Pad4)") (class "Default")
      (node (ref "X4") (pin "4") (pinfunction "4_4") (pintype "passive"))
    )
  )
)
